# Piezo_Driver_ASCII.net
KiCad netlist of a schematic drawn in Altium Designer
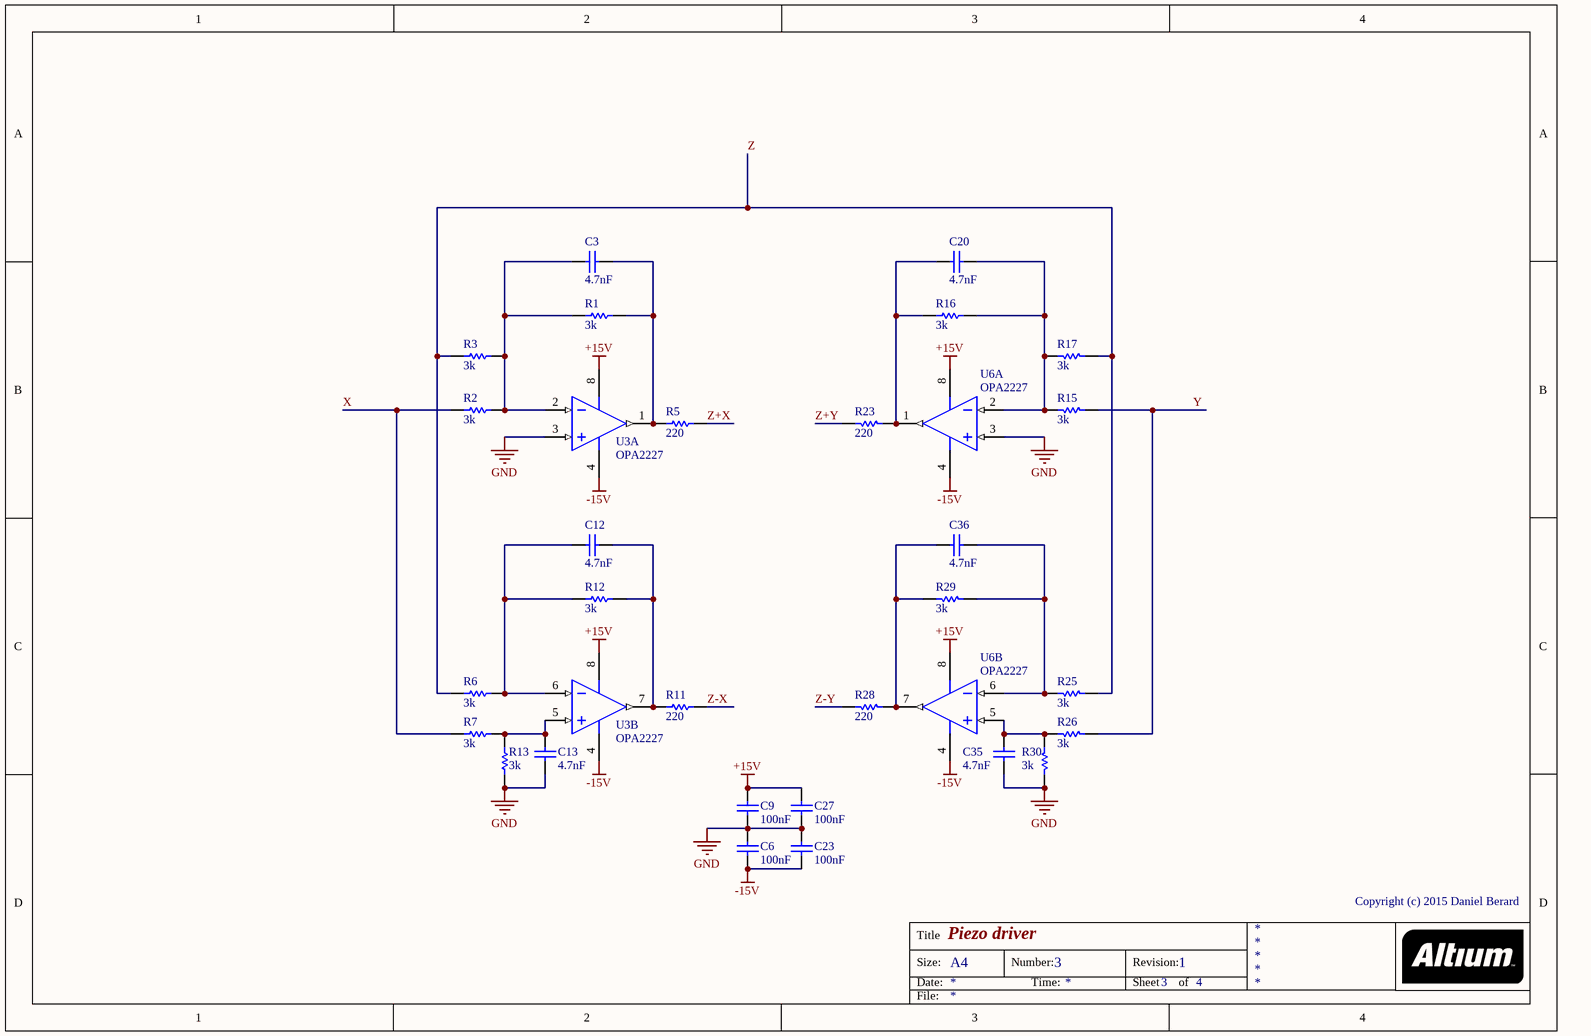
[diagram p0: Piezo Driver_ASCII.SchDoc]

(export (version "E")
  (design (tool "Eeschema 10.0.6"))
  (components
    (comp (ref "C3")
      (value "4.7nF")
      (footprint "6-0805_N")
      (description "Capacitor")
      (fields (field (name "PUBLISHER") "Altium Limited"))
      (libsource (lib "Miscellaneous Devices") (part "Cap"))
    )
    (comp (ref "C6")
      (value "100nF")
      (footprint "6-0805_N")
      (description "Capacitor")
      (fields (field (name "PUBLISHER") "Altium Limited"))
      (libsource (lib "Miscellaneous Devices") (part "Cap"))
    )
    (comp (ref "C9")
      (value "100nF")
      (footprint "6-0805_N")
      (description "Capacitor")
      (fields (field (name "PUBLISHER") "Altium Limited"))
      (libsource (lib "Miscellaneous Devices") (part "Cap"))
    )
    (comp (ref "C12")
      (value "4.7nF")
      (footprint "6-0805_N")
      (description "Capacitor")
      (fields (field (name "PUBLISHER") "Altium Limited"))
      (libsource (lib "Miscellaneous Devices") (part "Cap"))
    )
    (comp (ref "C13")
      (value "4.7nF")
      (footprint "6-0805_N")
      (description "Capacitor")
      (fields (field (name "PUBLISHER") "Altium Limited"))
      (libsource (lib "Miscellaneous Devices") (part "Cap"))
    )
    (comp (ref "C20")
      (value "4.7nF")
      (footprint "6-0805_N")
      (description "Capacitor")
      (fields (field (name "PUBLISHER") "Altium Limited"))
      (libsource (lib "Miscellaneous Devices") (part "Cap"))
    )
    (comp (ref "C23")
      (value "100nF")
      (footprint "6-0805_N")
      (description "Capacitor")
      (fields (field (name "PUBLISHER") "Altium Limited"))
      (libsource (lib "Miscellaneous Devices") (part "Cap"))
    )
    (comp (ref "C27")
      (value "100nF")
      (footprint "6-0805_N")
      (description "Capacitor")
      (fields (field (name "PUBLISHER") "Altium Limited"))
      (libsource (lib "Miscellaneous Devices") (part "Cap"))
    )
    (comp (ref "C35")
      (value "4.7nF")
      (footprint "6-0805_N")
      (description "Capacitor")
      (fields (field (name "PUBLISHER") "Altium Limited"))
      (libsource (lib "Miscellaneous Devices") (part "Cap"))
    )
    (comp (ref "C36")
      (value "4.7nF")
      (footprint "6-0805_N")
      (description "Capacitor")
      (fields (field (name "PUBLISHER") "Altium Limited"))
      (libsource (lib "Miscellaneous Devices") (part "Cap"))
    )
    (comp (ref "R1")
      (value "3k")
      (footprint "6-0805_N")
      (description "Resistor")
      (fields (field (name "PUBLISHER") "Altium Limited"))
      (libsource (lib "Miscellaneous Devices") (part "Res1"))
    )
    (comp (ref "R2")
      (value "3k")
      (footprint "6-0805_N")
      (description "Resistor")
      (fields (field (name "PUBLISHER") "Altium Limited"))
      (libsource (lib "Miscellaneous Devices") (part "Res1"))
    )
    (comp (ref "R3")
      (value "3k")
      (footprint "6-0805_N")
      (description "Resistor")
      (fields (field (name "PUBLISHER") "Altium Limited"))
      (libsource (lib "Miscellaneous Devices") (part "Res1"))
    )
    (comp (ref "R5")
      (value "220")
      (footprint "6-0805_N")
      (description "Resistor")
      (fields (field (name "PUBLISHER") "Altium Limited"))
      (libsource (lib "Miscellaneous Devices") (part "Res1"))
    )
    (comp (ref "R6")
      (value "3k")
      (footprint "6-0805_N")
      (description "Resistor")
      (fields (field (name "PUBLISHER") "Altium Limited"))
      (libsource (lib "Miscellaneous Devices") (part "Res1"))
    )
    (comp (ref "R7")
      (value "3k")
      (footprint "6-0805_N")
      (description "Resistor")
      (fields (field (name "PUBLISHER") "Altium Limited"))
      (libsource (lib "Miscellaneous Devices") (part "Res1"))
    )
    (comp (ref "R11")
      (value "220")
      (footprint "6-0805_N")
      (description "Resistor")
      (fields (field (name "PUBLISHER") "Altium Limited"))
      (libsource (lib "Miscellaneous Devices") (part "Res1"))
    )
    (comp (ref "R12")
      (value "3k")
      (footprint "6-0805_N")
      (description "Resistor")
      (fields (field (name "PUBLISHER") "Altium Limited"))
      (libsource (lib "Miscellaneous Devices") (part "Res1"))
    )
    (comp (ref "R13")
      (value "3k")
      (footprint "6-0805_N")
      (description "Resistor")
      (fields (field (name "PUBLISHER") "Altium Limited"))
      (libsource (lib "Miscellaneous Devices") (part "Res1"))
    )
    (comp (ref "R15")
      (value "3k")
      (footprint "6-0805_N")
      (description "Resistor")
      (fields (field (name "PUBLISHER") "Altium Limited"))
      (libsource (lib "Miscellaneous Devices") (part "Res1"))
    )
    (comp (ref "R16")
      (value "3k")
      (footprint "6-0805_N")
      (description "Resistor")
      (fields (field (name "PUBLISHER") "Altium Limited"))
      (libsource (lib "Miscellaneous Devices") (part "Res1"))
    )
    (comp (ref "R17")
      (value "3k")
      (footprint "6-0805_N")
      (description "Resistor")
      (fields (field (name "PUBLISHER") "Altium Limited"))
      (libsource (lib "Miscellaneous Devices") (part "Res1"))
    )
    (comp (ref "R23")
      (value "220")
      (footprint "6-0805_N")
      (description "Resistor")
      (fields (field (name "PUBLISHER") "Altium Limited"))
      (libsource (lib "Miscellaneous Devices") (part "Res1"))
    )
    (comp (ref "R25")
      (value "3k")
      (footprint "6-0805_N")
      (description "Resistor")
      (fields (field (name "PUBLISHER") "Altium Limited"))
      (libsource (lib "Miscellaneous Devices") (part "Res1"))
    )
    (comp (ref "R26")
      (value "3k")
      (footprint "6-0805_N")
      (description "Resistor")
      (fields (field (name "PUBLISHER") "Altium Limited"))
      (libsource (lib "Miscellaneous Devices") (part "Res1"))
    )
    (comp (ref "R28")
      (value "220")
      (footprint "6-0805_N")
      (description "Resistor")
      (fields (field (name "PUBLISHER") "Altium Limited"))
      (libsource (lib "Miscellaneous Devices") (part "Res1"))
    )
    (comp (ref "R29")
      (value "3k")
      (footprint "6-0805_N")
      (description "Resistor")
      (fields (field (name "PUBLISHER") "Altium Limited"))
      (libsource (lib "Miscellaneous Devices") (part "Res1"))
    )
    (comp (ref "R30")
      (value "3k")
      (footprint "6-0805_N")
      (description "Resistor")
      (fields (field (name "PUBLISHER") "Altium Limited"))
      (libsource (lib "Miscellaneous Devices") (part "Res1"))
    )
    (comp (ref "U3")
      (value "OPA2227")
      (footprint "ADI-R-8_M")
      (fields
        (field (name "MANUFACTURER") "Analog Devices")
        (field (name "GENERIC PART NUMBER") "AD8676")
        (field (name "PARTNUMBER") "AD8676BRZ")
      )
      (libsource (lib "Altium Content Vault") (part "CMP-0384-01147-2"))
    )
    (comp (ref "U6")
      (value "OPA2227")
      (footprint "ADI-R-8_M")
      (fields
        (field (name "MANUFACTURER") "Analog Devices")
        (field (name "GENERIC PART NUMBER") "AD8676")
        (field (name "PARTNUMBER") "AD8676BRZ")
      )
      (libsource (lib "Altium Content Vault") (part "CMP-0384-01147-2"))
    )
  )
  (nets
    (net (code "1") (name "+15V") (class "Default")
      (node (ref "C27") (pin "2") (pinfunction "2_2") (pintype "passive"))
      (node (ref "C9") (pin "2") (pinfunction "2_2") (pintype "passive"))
      (node (ref "U3") (pin "8") (pinfunction "+V_8") (pintype "power_in"))
      (node (ref "U6") (pin "8") (pinfunction "+V_8") (pintype "power_in"))
    )
    (net (code "2") (name "-15V") (class "Default")
      (node (ref "C23") (pin "1") (pinfunction "1_1") (pintype "passive"))
      (node (ref "C6") (pin "1") (pinfunction "1_1") (pintype "passive"))
      (node (ref "U3") (pin "4") (pinfunction "-V_4") (pintype "power_in"))
      (node (ref "U6") (pin "4") (pinfunction "-V_4") (pintype "power_in"))
    )
    (net (code "3") (name "/X") (class "Default")
      (node (ref "R2") (pin "1") (pinfunction "1_1") (pintype "passive"))
      (node (ref "R7") (pin "1") (pinfunction "1_1") (pintype "passive"))
    )
    (net (code "4") (name "/Y") (class "Default")
      (node (ref "R15") (pin "1") (pinfunction "1_1") (pintype "passive"))
      (node (ref "R26") (pin "1") (pinfunction "1_1") (pintype "passive"))
    )
    (net (code "5") (name "/Z") (class "Default")
      (node (ref "R17") (pin "1") (pinfunction "1_1") (pintype "passive"))
      (node (ref "R25") (pin "1") (pinfunction "1_1") (pintype "passive"))
      (node (ref "R3") (pin "1") (pinfunction "1_1") (pintype "passive"))
      (node (ref "R6") (pin "1") (pinfunction "1_1") (pintype "passive"))
    )
    (net (code "6") (name "/Z+X") (class "Default")
      (node (ref "R5") (pin "2") (pinfunction "2_2") (pintype "passive"))
    )
    (net (code "7") (name "/Z+Y") (class "Default")
      (node (ref "R23") (pin "2") (pinfunction "2_2") (pintype "passive"))
    )
    (net (code "8") (name "/Z-X") (class "Default")
      (node (ref "R11") (pin "2") (pinfunction "2_2") (pintype "passive"))
    )
    (net (code "9") (name "/Z-Y") (class "Default")
      (node (ref "R28") (pin "2") (pinfunction "2_2") (pintype "passive"))
    )
    (net (code "10") (name "GND") (class "Default")
      (node (ref "C13") (pin "1") (pinfunction "1_1") (pintype "passive"))
      (node (ref "C23") (pin "2") (pinfunction "2_2") (pintype "passive"))
      (node (ref "C27") (pin "1") (pinfunction "1_1") (pintype "passive"))
      (node (ref "C35") (pin "1") (pinfunction "1_1") (pintype "passive"))
      (node (ref "C6") (pin "2") (pinfunction "2_2") (pintype "passive"))
      (node (ref "C9") (pin "1") (pinfunction "1_1") (pintype "passive"))
      (node (ref "R13") (pin "1") (pinfunction "1_1") (pintype "passive"))
      (node (ref "R30") (pin "1") (pinfunction "1_1") (pintype "passive"))
      (node (ref "U3") (pin "3") (pinfunction "+IN_A_3") (pintype "input"))
      (node (ref "U6") (pin "3") (pinfunction "+IN_A_3") (pintype "input"))
    )
    (net (code "11") (name "Net-(U3A--IN_A)") (class "Default")
      (node (ref "C3") (pin "1") (pinfunction "1_1") (pintype "passive"))
      (node (ref "R1") (pin "1") (pinfunction "1_1") (pintype "passive"))
      (node (ref "R2") (pin "2") (pinfunction "2_2") (pintype "passive"))
      (node (ref "R3") (pin "2") (pinfunction "2_2") (pintype "passive"))
      (node (ref "U3") (pin "2") (pinfunction "-IN_A_2") (pintype "input"))
    )
    (net (code "12") (name "Net-(U3A-OUT_A)") (class "Default")
      (node (ref "C3") (pin "2") (pinfunction "2_2") (pintype "passive"))
      (node (ref "R1") (pin "2") (pinfunction "2_2") (pintype "passive"))
      (node (ref "R5") (pin "1") (pinfunction "1_1") (pintype "passive"))
      (node (ref "U3") (pin "1") (pinfunction "OUT_A_1") (pintype "output"))
    )
    (net (code "13") (name "Net-(U3B-+IN_B)") (class "Default")
      (node (ref "C13") (pin "2") (pinfunction "2_2") (pintype "passive"))
      (node (ref "R13") (pin "2") (pinfunction "2_2") (pintype "passive"))
      (node (ref "R7") (pin "2") (pinfunction "2_2") (pintype "passive"))
      (node (ref "U3") (pin "5") (pinfunction "+IN_B_5") (pintype "input"))
    )
    (net (code "14") (name "Net-(U3B--IN_B)") (class "Default")
      (node (ref "C12") (pin "1") (pinfunction "1_1") (pintype "passive"))
      (node (ref "R12") (pin "1") (pinfunction "1_1") (pintype "passive"))
      (node (ref "R6") (pin "2") (pinfunction "2_2") (pintype "passive"))
      (node (ref "U3") (pin "6") (pinfunction "-IN_B_6") (pintype "input"))
    )
    (net (code "15") (name "Net-(U3B-OUT_B)") (class "Default")
      (node (ref "C12") (pin "2") (pinfunction "2_2") (pintype "passive"))
      (node (ref "R11") (pin "1") (pinfunction "1_1") (pintype "passive"))
      (node (ref "R12") (pin "2") (pinfunction "2_2") (pintype "passive"))
      (node (ref "U3") (pin "7") (pinfunction "OUT_B_7") (pintype "output"))
    )
    (net (code "16") (name "Net-(U6A--IN_A)") (class "Default")
      (node (ref "C20") (pin "2") (pinfunction "2_2") (pintype "passive"))
      (node (ref "R15") (pin "2") (pinfunction "2_2") (pintype "passive"))
      (node (ref "R16") (pin "2") (pinfunction "2_2") (pintype "passive"))
      (node (ref "R17") (pin "2") (pinfunction "2_2") (pintype "passive"))
      (node (ref "U6") (pin "2") (pinfunction "-IN_A_2") (pintype "input"))
    )
    (net (code "17") (name "Net-(U6A-OUT_A)") (class "Default")
      (node (ref "C20") (pin "1") (pinfunction "1_1") (pintype "passive"))
      (node (ref "R16") (pin "1") (pinfunction "1_1") (pintype "passive"))
      (node (ref "R23") (pin "1") (pinfunction "1_1") (pintype "passive"))
      (node (ref "U6") (pin "1") (pinfunction "OUT_A_1") (pintype "output"))
    )
    (net (code "18") (name "Net-(U6B-+IN_B)") (class "Default")
      (node (ref "C35") (pin "2") (pinfunction "2_2") (pintype "passive"))
      (node (ref "R26") (pin "2") (pinfunction "2_2") (pintype "passive"))
      (node (ref "R30") (pin "2") (pinfunction "2_2") (pintype "passive"))
      (node (ref "U6") (pin "5") (pinfunction "+IN_B_5") (pintype "input"))
    )
    (net (code "19") (name "Net-(U6B--IN_B)") (class "Default")
      (node (ref "C36") (pin "2") (pinfunction "2_2") (pintype "passive"))
      (node (ref "R25") (pin "2") (pinfunction "2_2") (pintype "passive"))
      (node (ref "R29") (pin "1") (pinfunction "1_1") (pintype "passive"))
      (node (ref "U6") (pin "6") (pinfunction "-IN_B_6") (pintype "input"))
    )
    (net (code "20") (name "Net-(U6B-OUT_B)") (class "Default")
      (node (ref "C36") (pin "1") (pinfunction "1_1") (pintype "passive"))
      (node (ref "R28") (pin "1") (pinfunction "1_1") (pintype "passive"))
      (node (ref "R29") (pin "2") (pinfunction "2_2") (pintype "passive"))
      (node (ref "U6") (pin "7") (pinfunction "OUT_B_7") (pintype "output"))
    )
  )
)
